# digit_mini.net
KiCad netlist of a schematic drawn in EAGLE
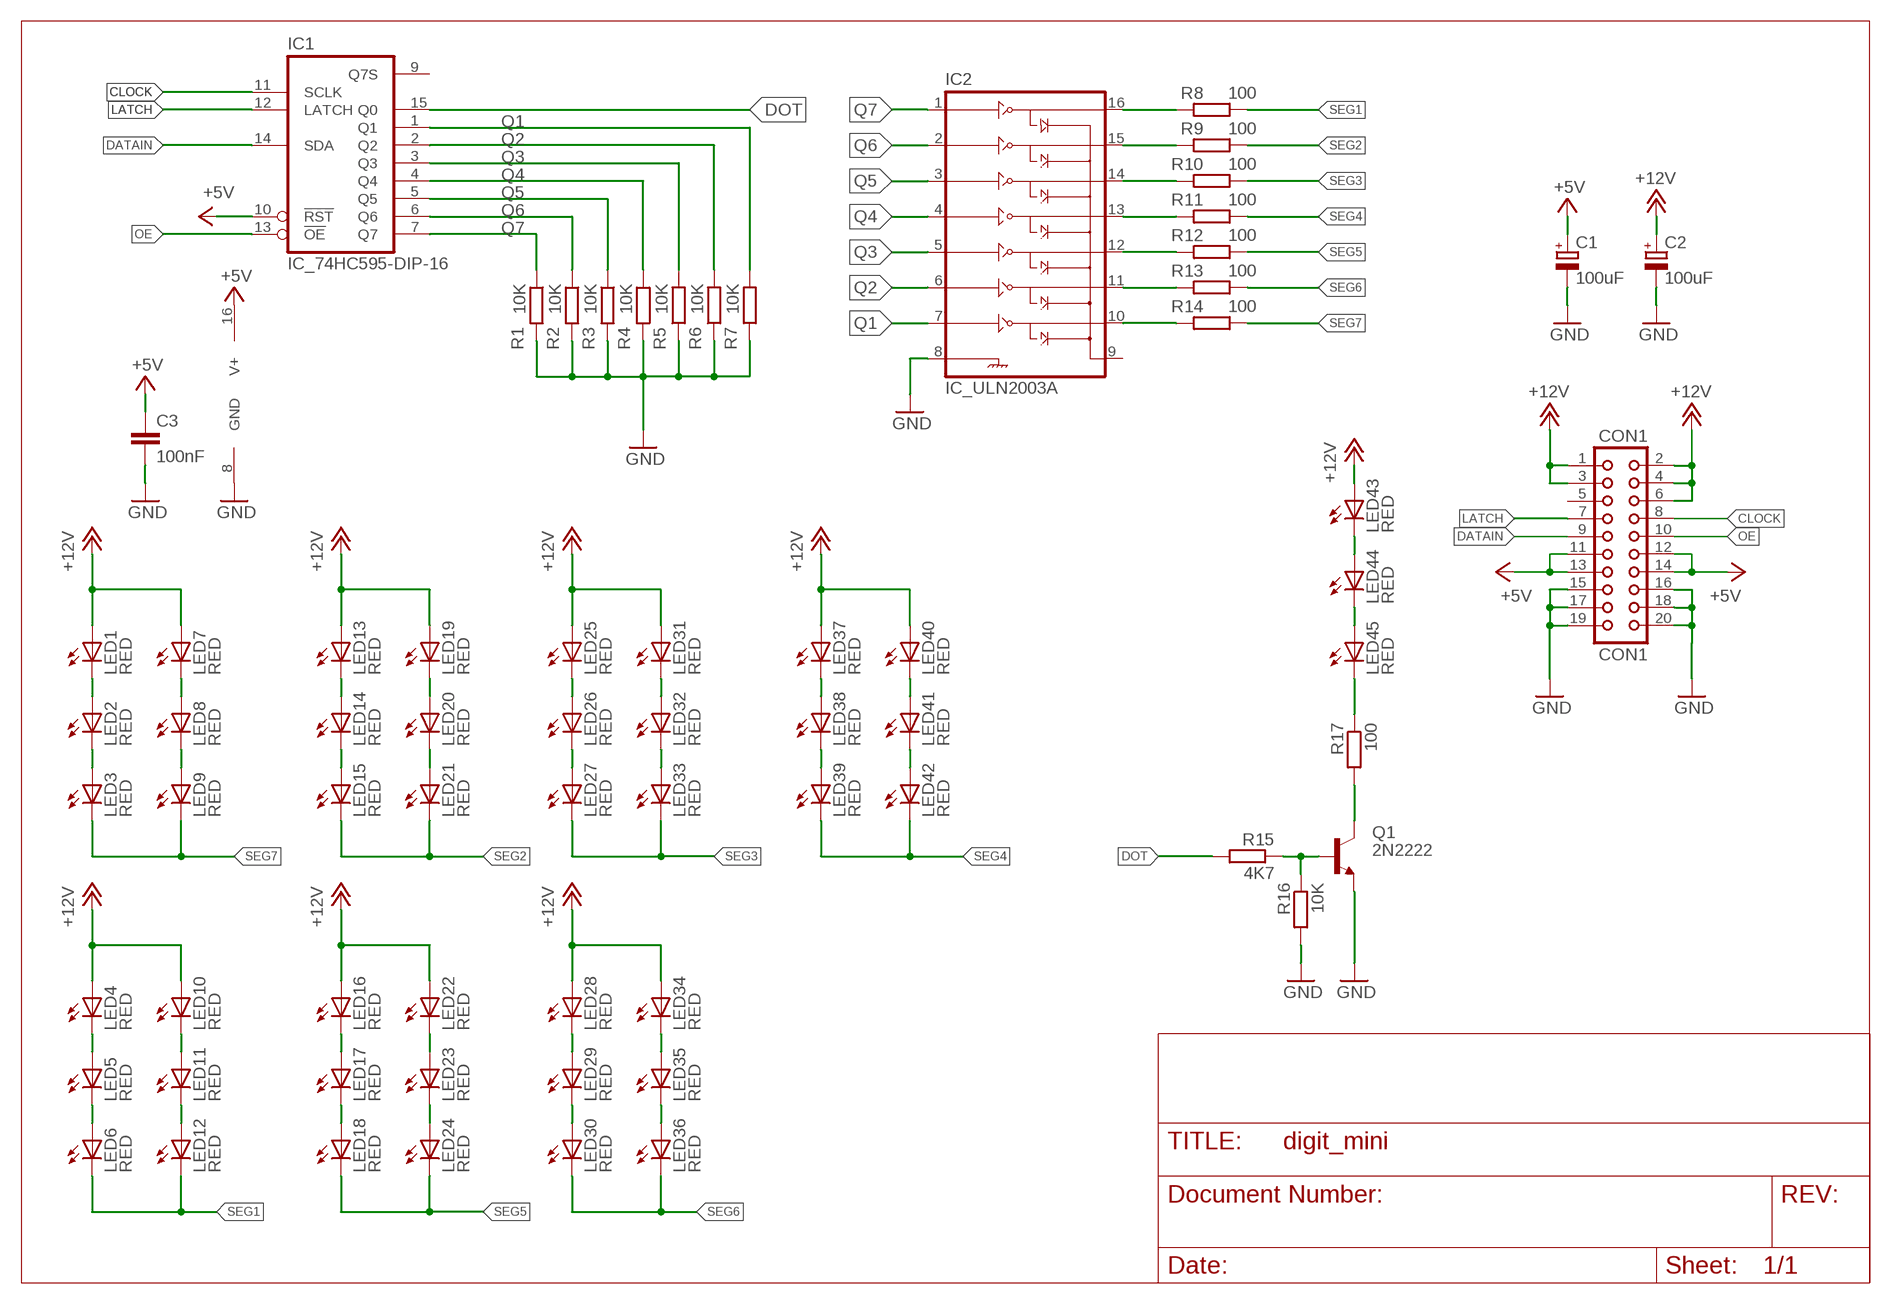
[diagram p0: schematic, sheet 1]

(export (version "E")
  (design (tool "Eeschema 10.0.6"))
  (components
    (comp (ref "C1")
      (value "100uF")
      (footprint "eagle-import:E2,5-7")
      (libsource (lib "eagle-import") (part "CPOL-EUE2.5-7"))
    )
    (comp (ref "C2")
      (value "100uF")
      (footprint "eagle-import:E2,5-7")
      (libsource (lib "eagle-import") (part "CPOL-EUE2.5-7"))
    )
    (comp (ref "C3")
      (value "100nF")
      (footprint "eagle-import:C050-025X075")
      (libsource (lib "eagle-import") (part "C-EU050-025X075"))
    )
    (comp (ref "CON1")
      (value "CON1")
      (footprint "eagle-import:CON20")
      (libsource (lib "eagle-import") (part "CON20"))
    )
    (comp (ref "IC1")
      (value "IC_74HC595-DIP-16")
      (footprint "eagle-import:DIL16")
      (libsource (lib "eagle-import") (part "IC_74HC595-DIP-16"))
    )
    (comp (ref "IC2")
      (value "IC_ULN2003A")
      (footprint "eagle-import:DIL16")
      (libsource (lib "eagle-import") (part "IC_ULN2003A"))
    )
    (comp (ref "LED1")
      (value "RED")
      (footprint "eagle-import:LED5MM")
      (libsource (lib "eagle-import") (part "LED5MM"))
    )
    (comp (ref "LED2")
      (value "RED")
      (footprint "eagle-import:LED5MM")
      (libsource (lib "eagle-import") (part "LED5MM"))
    )
    (comp (ref "LED3")
      (value "RED")
      (footprint "eagle-import:LED5MM")
      (libsource (lib "eagle-import") (part "LED5MM"))
    )
    (comp (ref "LED4")
      (value "RED")
      (footprint "eagle-import:LED5MM")
      (libsource (lib "eagle-import") (part "LED5MM"))
    )
    (comp (ref "LED5")
      (value "RED")
      (footprint "eagle-import:LED5MM")
      (libsource (lib "eagle-import") (part "LED5MM"))
    )
    (comp (ref "LED6")
      (value "RED")
      (footprint "eagle-import:LED5MM")
      (libsource (lib "eagle-import") (part "LED5MM"))
    )
    (comp (ref "LED7")
      (value "RED")
      (footprint "eagle-import:LED5MM")
      (libsource (lib "eagle-import") (part "LED5MM"))
    )
    (comp (ref "LED8")
      (value "RED")
      (footprint "eagle-import:LED5MM")
      (libsource (lib "eagle-import") (part "LED5MM"))
    )
    (comp (ref "LED9")
      (value "RED")
      (footprint "eagle-import:LED5MM")
      (libsource (lib "eagle-import") (part "LED5MM"))
    )
    (comp (ref "LED10")
      (value "RED")
      (footprint "eagle-import:LED5MM")
      (libsource (lib "eagle-import") (part "LED5MM"))
    )
    (comp (ref "LED11")
      (value "RED")
      (footprint "eagle-import:LED5MM")
      (libsource (lib "eagle-import") (part "LED5MM"))
    )
    (comp (ref "LED12")
      (value "RED")
      (footprint "eagle-import:LED5MM")
      (libsource (lib "eagle-import") (part "LED5MM"))
    )
    (comp (ref "LED13")
      (value "RED")
      (footprint "eagle-import:LED5MM")
      (libsource (lib "eagle-import") (part "LED5MM"))
    )
    (comp (ref "LED14")
      (value "RED")
      (footprint "eagle-import:LED5MM")
      (libsource (lib "eagle-import") (part "LED5MM"))
    )
    (comp (ref "LED15")
      (value "RED")
      (footprint "eagle-import:LED5MM")
      (libsource (lib "eagle-import") (part "LED5MM"))
    )
    (comp (ref "LED16")
      (value "RED")
      (footprint "eagle-import:LED5MM")
      (libsource (lib "eagle-import") (part "LED5MM"))
    )
    (comp (ref "LED17")
      (value "RED")
      (footprint "eagle-import:LED5MM")
      (libsource (lib "eagle-import") (part "LED5MM"))
    )
    (comp (ref "LED18")
      (value "RED")
      (footprint "eagle-import:LED5MM")
      (libsource (lib "eagle-import") (part "LED5MM"))
    )
    (comp (ref "LED19")
      (value "RED")
      (footprint "eagle-import:LED5MM")
      (libsource (lib "eagle-import") (part "LED5MM"))
    )
    (comp (ref "LED20")
      (value "RED")
      (footprint "eagle-import:LED5MM")
      (libsource (lib "eagle-import") (part "LED5MM"))
    )
    (comp (ref "LED21")
      (value "RED")
      (footprint "eagle-import:LED5MM")
      (libsource (lib "eagle-import") (part "LED5MM"))
    )
    (comp (ref "LED22")
      (value "RED")
      (footprint "eagle-import:LED5MM")
      (libsource (lib "eagle-import") (part "LED5MM"))
    )
    (comp (ref "LED23")
      (value "RED")
      (footprint "eagle-import:LED5MM")
      (libsource (lib "eagle-import") (part "LED5MM"))
    )
    (comp (ref "LED24")
      (value "RED")
      (footprint "eagle-import:LED5MM")
      (libsource (lib "eagle-import") (part "LED5MM"))
    )
    (comp (ref "LED25")
      (value "RED")
      (footprint "eagle-import:LED5MM")
      (libsource (lib "eagle-import") (part "LED5MM"))
    )
    (comp (ref "LED26")
      (value "RED")
      (footprint "eagle-import:LED5MM")
      (libsource (lib "eagle-import") (part "LED5MM"))
    )
    (comp (ref "LED27")
      (value "RED")
      (footprint "eagle-import:LED5MM")
      (libsource (lib "eagle-import") (part "LED5MM"))
    )
    (comp (ref "LED28")
      (value "RED")
      (footprint "eagle-import:LED5MM")
      (libsource (lib "eagle-import") (part "LED5MM"))
    )
    (comp (ref "LED29")
      (value "RED")
      (footprint "eagle-import:LED5MM")
      (libsource (lib "eagle-import") (part "LED5MM"))
    )
    (comp (ref "LED30")
      (value "RED")
      (footprint "eagle-import:LED5MM")
      (libsource (lib "eagle-import") (part "LED5MM"))
    )
    (comp (ref "LED31")
      (value "RED")
      (footprint "eagle-import:LED5MM")
      (libsource (lib "eagle-import") (part "LED5MM"))
    )
    (comp (ref "LED32")
      (value "RED")
      (footprint "eagle-import:LED5MM")
      (libsource (lib "eagle-import") (part "LED5MM"))
    )
    (comp (ref "LED33")
      (value "RED")
      (footprint "eagle-import:LED5MM")
      (libsource (lib "eagle-import") (part "LED5MM"))
    )
    (comp (ref "LED34")
      (value "RED")
      (footprint "eagle-import:LED5MM")
      (libsource (lib "eagle-import") (part "LED5MM"))
    )
    (comp (ref "LED35")
      (value "RED")
      (footprint "eagle-import:LED5MM")
      (libsource (lib "eagle-import") (part "LED5MM"))
    )
    (comp (ref "LED36")
      (value "RED")
      (footprint "eagle-import:LED5MM")
      (libsource (lib "eagle-import") (part "LED5MM"))
    )
    (comp (ref "LED37")
      (value "RED")
      (footprint "eagle-import:LED5MM")
      (libsource (lib "eagle-import") (part "LED5MM"))
    )
    (comp (ref "LED38")
      (value "RED")
      (footprint "eagle-import:LED5MM")
      (libsource (lib "eagle-import") (part "LED5MM"))
    )
    (comp (ref "LED39")
      (value "RED")
      (footprint "eagle-import:LED5MM")
      (libsource (lib "eagle-import") (part "LED5MM"))
    )
    (comp (ref "LED40")
      (value "RED")
      (footprint "eagle-import:LED5MM")
      (libsource (lib "eagle-import") (part "LED5MM"))
    )
    (comp (ref "LED41")
      (value "RED")
      (footprint "eagle-import:LED5MM")
      (libsource (lib "eagle-import") (part "LED5MM"))
    )
    (comp (ref "LED42")
      (value "RED")
      (footprint "eagle-import:LED5MM")
      (libsource (lib "eagle-import") (part "LED5MM"))
    )
    (comp (ref "LED43")
      (value "RED")
      (footprint "eagle-import:LED5MM")
      (libsource (lib "eagle-import") (part "LED5MM"))
    )
    (comp (ref "LED44")
      (value "RED")
      (footprint "eagle-import:LED5MM")
      (libsource (lib "eagle-import") (part "LED5MM"))
    )
    (comp (ref "LED45")
      (value "RED")
      (footprint "eagle-import:LED5MM")
      (libsource (lib "eagle-import") (part "LED5MM"))
    )
    (comp (ref "Q1")
      (value "2N2222")
      (footprint "eagle-import:TO92-E1")
      (libsource (lib "eagle-import") (part "-NPN-TO92-E1"))
    )
    (comp (ref "R1")
      (value "10K")
      (footprint "eagle-import:0207_12")
      (libsource (lib "eagle-import") (part "R-EU_0207/12"))
    )
    (comp (ref "R2")
      (value "10K")
      (footprint "eagle-import:0207_12")
      (libsource (lib "eagle-import") (part "R-EU_0207/12"))
    )
    (comp (ref "R3")
      (value "10K")
      (footprint "eagle-import:0207_12")
      (libsource (lib "eagle-import") (part "R-EU_0207/12"))
    )
    (comp (ref "R4")
      (value "10K")
      (footprint "eagle-import:0207_12")
      (libsource (lib "eagle-import") (part "R-EU_0207/12"))
    )
    (comp (ref "R5")
      (value "10K")
      (footprint "eagle-import:0207_12")
      (libsource (lib "eagle-import") (part "R-EU_0207/12"))
    )
    (comp (ref "R6")
      (value "10K")
      (footprint "eagle-import:0207_12")
      (libsource (lib "eagle-import") (part "R-EU_0207/12"))
    )
    (comp (ref "R7")
      (value "10K")
      (footprint "eagle-import:0207_12")
      (libsource (lib "eagle-import") (part "R-EU_0207/12"))
    )
    (comp (ref "R8")
      (value "100")
      (footprint "eagle-import:0207_12")
      (libsource (lib "eagle-import") (part "R-EU_0207/12"))
    )
    (comp (ref "R9")
      (value "100")
      (footprint "eagle-import:0207_12")
      (libsource (lib "eagle-import") (part "R-EU_0207/12"))
    )
    (comp (ref "R10")
      (value "100")
      (footprint "eagle-import:0207_12")
      (libsource (lib "eagle-import") (part "R-EU_0207/12"))
    )
    (comp (ref "R11")
      (value "100")
      (footprint "eagle-import:0207_12")
      (libsource (lib "eagle-import") (part "R-EU_0207/12"))
    )
    (comp (ref "R12")
      (value "100")
      (footprint "eagle-import:0207_12")
      (libsource (lib "eagle-import") (part "R-EU_0207/12"))
    )
    (comp (ref "R13")
      (value "100")
      (footprint "eagle-import:0207_12")
      (libsource (lib "eagle-import") (part "R-EU_0207/12"))
    )
    (comp (ref "R14")
      (value "100")
      (footprint "eagle-import:0207_12")
      (libsource (lib "eagle-import") (part "R-EU_0207/12"))
    )
    (comp (ref "R15")
      (value "4K7")
      (footprint "eagle-import:0207_12")
      (libsource (lib "eagle-import") (part "R-EU_0207/12"))
    )
    (comp (ref "R16")
      (value "10K")
      (footprint "eagle-import:0207_12")
      (libsource (lib "eagle-import") (part "R-EU_0207/12"))
    )
    (comp (ref "R17")
      (value "100")
      (footprint "eagle-import:0207_12")
      (libsource (lib "eagle-import") (part "R-EU_0207/12"))
    )
  )
  (nets
    (net (code "1") (name "+5V") (class "Default")
      (node (ref "C1") (pin "+") (pinfunction "+_+") (pintype "passive"))
      (node (ref "C3") (pin "1") (pinfunction "1_1") (pintype "passive"))
      (node (ref "CON1") (pin "11") (pinfunction "11_11") (pintype "passive"))
      (node (ref "CON1") (pin "12") (pinfunction "12_12") (pintype "passive"))
      (node (ref "CON1") (pin "13") (pinfunction "13_13") (pintype "passive"))
      (node (ref "CON1") (pin "14") (pinfunction "14_14") (pintype "passive"))
      (node (ref "IC1") (pin "10") (pinfunction "~{RST}_10") (pintype "input"))
      (node (ref "IC1") (pin "16") (pinfunction "V+_16") (pintype "power_in"))
    )
    (net (code "2") (name "+12V") (class "Default")
      (node (ref "C2") (pin "+") (pinfunction "+_+") (pintype "passive"))
      (node (ref "CON1") (pin "1") (pinfunction "1_1") (pintype "passive"))
      (node (ref "CON1") (pin "2") (pinfunction "2_2") (pintype "passive"))
      (node (ref "CON1") (pin "3") (pinfunction "3_3") (pintype "passive"))
      (node (ref "CON1") (pin "4") (pinfunction "4_4") (pintype "passive"))
      (node (ref "CON1") (pin "6") (pinfunction "6_6") (pintype "passive"))
      (node (ref "LED1") (pin "A") (pinfunction "A_A") (pintype "passive"))
      (node (ref "LED10") (pin "A") (pinfunction "A_A") (pintype "passive"))
      (node (ref "LED13") (pin "A") (pinfunction "A_A") (pintype "passive"))
      (node (ref "LED16") (pin "A") (pinfunction "A_A") (pintype "passive"))
      (node (ref "LED19") (pin "A") (pinfunction "A_A") (pintype "passive"))
      (node (ref "LED22") (pin "A") (pinfunction "A_A") (pintype "passive"))
      (node (ref "LED25") (pin "A") (pinfunction "A_A") (pintype "passive"))
      (node (ref "LED28") (pin "A") (pinfunction "A_A") (pintype "passive"))
      (node (ref "LED31") (pin "A") (pinfunction "A_A") (pintype "passive"))
      (node (ref "LED34") (pin "A") (pinfunction "A_A") (pintype "passive"))
      (node (ref "LED37") (pin "A") (pinfunction "A_A") (pintype "passive"))
      (node (ref "LED4") (pin "A") (pinfunction "A_A") (pintype "passive"))
      (node (ref "LED40") (pin "A") (pinfunction "A_A") (pintype "passive"))
      (node (ref "LED43") (pin "A") (pinfunction "A_A") (pintype "passive"))
      (node (ref "LED7") (pin "A") (pinfunction "A_A") (pintype "passive"))
    )
    (net (code "3") (name "CLOCK") (class "Default")
      (node (ref "CON1") (pin "8") (pinfunction "8_8") (pintype "passive"))
      (node (ref "IC1") (pin "11") (pinfunction "SCLK_11") (pintype "input"))
    )
    (net (code "4") (name "DATAIN") (class "Default")
      (node (ref "CON1") (pin "9") (pinfunction "9_9") (pintype "passive"))
      (node (ref "IC1") (pin "14") (pinfunction "SDA_14") (pintype "input"))
    )
    (net (code "5") (name "DOT") (class "Default")
      (node (ref "IC1") (pin "15") (pinfunction "Q0_15") (pintype "output"))
      (node (ref "R15") (pin "2") (pinfunction "2_2") (pintype "passive"))
    )
    (net (code "6") (name "GND") (class "Default")
      (node (ref "C1") (pin "-") (pinfunction "-_-") (pintype "passive"))
      (node (ref "C2") (pin "-") (pinfunction "-_-") (pintype "passive"))
      (node (ref "C3") (pin "2") (pinfunction "2_2") (pintype "passive"))
      (node (ref "CON1") (pin "15") (pinfunction "15_15") (pintype "passive"))
      (node (ref "CON1") (pin "16") (pinfunction "16_16") (pintype "passive"))
      (node (ref "CON1") (pin "17") (pinfunction "17_17") (pintype "passive"))
      (node (ref "CON1") (pin "18") (pinfunction "18_18") (pintype "passive"))
      (node (ref "CON1") (pin "19") (pinfunction "19_19") (pintype "passive"))
      (node (ref "CON1") (pin "20") (pinfunction "20_20") (pintype "passive"))
      (node (ref "IC1") (pin "8") (pinfunction "GND_8") (pintype "power_in"))
      (node (ref "IC2") (pin "8") (pinfunction "GND_8") (pintype "bidirectional"))
      (node (ref "Q1") (pin "3") (pinfunction "E_3") (pintype "passive"))
      (node (ref "R1") (pin "2") (pinfunction "2_2") (pintype "passive"))
      (node (ref "R16") (pin "2") (pinfunction "2_2") (pintype "passive"))
      (node (ref "R2") (pin "2") (pinfunction "2_2") (pintype "passive"))
      (node (ref "R3") (pin "2") (pinfunction "2_2") (pintype "passive"))
      (node (ref "R4") (pin "1") (pinfunction "1_1") (pintype "passive"))
      (node (ref "R5") (pin "1") (pinfunction "1_1") (pintype "passive"))
      (node (ref "R6") (pin "1") (pinfunction "1_1") (pintype "passive"))
      (node (ref "R7") (pin "1") (pinfunction "1_1") (pintype "passive"))
    )
    (net (code "7") (name "LATCH") (class "Default")
      (node (ref "CON1") (pin "7") (pinfunction "7_7") (pintype "passive"))
      (node (ref "IC1") (pin "12") (pinfunction "LATCH_12") (pintype "input"))
    )
    (net (code "8") (name "Net-(IC2-1C)") (class "Default")
      (node (ref "IC2") (pin "16") (pinfunction "1C_16") (pintype "bidirectional"))
      (node (ref "R8") (pin "2") (pinfunction "2_2") (pintype "passive"))
    )
    (net (code "9") (name "Net-(IC2-2C)") (class "Default")
      (node (ref "IC2") (pin "15") (pinfunction "2C_15") (pintype "bidirectional"))
      (node (ref "R9") (pin "2") (pinfunction "2_2") (pintype "passive"))
    )
    (net (code "10") (name "Net-(IC2-3C)") (class "Default")
      (node (ref "IC2") (pin "14") (pinfunction "3C_14") (pintype "bidirectional"))
      (node (ref "R10") (pin "2") (pinfunction "2_2") (pintype "passive"))
    )
    (net (code "11") (name "Net-(IC2-4C)") (class "Default")
      (node (ref "IC2") (pin "13") (pinfunction "4C_13") (pintype "bidirectional"))
      (node (ref "R11") (pin "2") (pinfunction "2_2") (pintype "passive"))
    )
    (net (code "12") (name "Net-(IC2-5C)") (class "Default")
      (node (ref "IC2") (pin "12") (pinfunction "5C_12") (pintype "bidirectional"))
      (node (ref "R12") (pin "2") (pinfunction "2_2") (pintype "passive"))
    )
    (net (code "13") (name "Net-(IC2-6C)") (class "Default")
      (node (ref "IC2") (pin "11") (pinfunction "6C_11") (pintype "bidirectional"))
      (node (ref "R13") (pin "2") (pinfunction "2_2") (pintype "passive"))
    )
    (net (code "14") (name "Net-(IC2-7C)") (class "Default")
      (node (ref "IC2") (pin "10") (pinfunction "7C_10") (pintype "bidirectional"))
      (node (ref "R14") (pin "2") (pinfunction "2_2") (pintype "passive"))
    )
    (net (code "15") (name "Net-(LED1-C)") (class "Default")
      (node (ref "LED1") (pin "K") (pinfunction "C_K") (pintype "passive"))
      (node (ref "LED2") (pin "A") (pinfunction "A_A") (pintype "passive"))
    )
    (net (code "16") (name "Net-(LED2-C)") (class "Default")
      (node (ref "LED2") (pin "K") (pinfunction "C_K") (pintype "passive"))
      (node (ref "LED3") (pin "A") (pinfunction "A_A") (pintype "passive"))
    )
    (net (code "17") (name "Net-(LED4-C)") (class "Default")
      (node (ref "LED4") (pin "K") (pinfunction "C_K") (pintype "passive"))
      (node (ref "LED5") (pin "A") (pinfunction "A_A") (pintype "passive"))
    )
    (net (code "18") (name "Net-(LED5-C)") (class "Default")
      (node (ref "LED5") (pin "K") (pinfunction "C_K") (pintype "passive"))
      (node (ref "LED6") (pin "A") (pinfunction "A_A") (pintype "passive"))
    )
    (net (code "19") (name "Net-(LED7-C)") (class "Default")
      (node (ref "LED7") (pin "K") (pinfunction "C_K") (pintype "passive"))
      (node (ref "LED8") (pin "A") (pinfunction "A_A") (pintype "passive"))
    )
    (net (code "20") (name "Net-(LED8-C)") (class "Default")
      (node (ref "LED8") (pin "K") (pinfunction "C_K") (pintype "passive"))
      (node (ref "LED9") (pin "A") (pinfunction "A_A") (pintype "passive"))
    )
    (net (code "21") (name "Net-(LED10-C)") (class "Default")
      (node (ref "LED10") (pin "K") (pinfunction "C_K") (pintype "passive"))
      (node (ref "LED11") (pin "A") (pinfunction "A_A") (pintype "passive"))
    )
    (net (code "22") (name "Net-(LED11-C)") (class "Default")
      (node (ref "LED11") (pin "K") (pinfunction "C_K") (pintype "passive"))
      (node (ref "LED12") (pin "A") (pinfunction "A_A") (pintype "passive"))
    )
    (net (code "23") (name "Net-(LED13-C)") (class "Default")
      (node (ref "LED13") (pin "K") (pinfunction "C_K") (pintype "passive"))
      (node (ref "LED14") (pin "A") (pinfunction "A_A") (pintype "passive"))
    )
    (net (code "24") (name "Net-(LED14-C)") (class "Default")
      (node (ref "LED14") (pin "K") (pinfunction "C_K") (pintype "passive"))
      (node (ref "LED15") (pin "A") (pinfunction "A_A") (pintype "passive"))
    )
    (net (code "25") (name "Net-(LED16-C)") (class "Default")
      (node (ref "LED16") (pin "K") (pinfunction "C_K") (pintype "passive"))
      (node (ref "LED17") (pin "A") (pinfunction "A_A") (pintype "passive"))
    )
    (net (code "26") (name "Net-(LED17-C)") (class "Default")
      (node (ref "LED17") (pin "K") (pinfunction "C_K") (pintype "passive"))
      (node (ref "LED18") (pin "A") (pinfunction "A_A") (pintype "passive"))
    )
    (net (code "27") (name "Net-(LED19-C)") (class "Default")
      (node (ref "LED19") (pin "K") (pinfunction "C_K") (pintype "passive"))
      (node (ref "LED20") (pin "A") (pinfunction "A_A") (pintype "passive"))
    )
    (net (code "28") (name "Net-(LED20-C)") (class "Default")
      (node (ref "LED20") (pin "K") (pinfunction "C_K") (pintype "passive"))
      (node (ref "LED21") (pin "A") (pinfunction "A_A") (pintype "passive"))
    )
    (net (code "29") (name "Net-(LED22-C)") (class "Default")
      (node (ref "LED22") (pin "K") (pinfunction "C_K") (pintype "passive"))
      (node (ref "LED23") (pin "A") (pinfunction "A_A") (pintype "passive"))
    )
    (net (code "30") (name "Net-(LED23-C)") (class "Default")
      (node (ref "LED23") (pin "K") (pinfunction "C_K") (pintype "passive"))
      (node (ref "LED24") (pin "A") (pinfunction "A_A") (pintype "passive"))
    )
    (net (code "31") (name "Net-(LED25-C)") (class "Default")
      (node (ref "LED25") (pin "K") (pinfunction "C_K") (pintype "passive"))
      (node (ref "LED26") (pin "A") (pinfunction "A_A") (pintype "passive"))
    )
    (net (code "32") (name "Net-(LED26-C)") (class "Default")
      (node (ref "LED26") (pin "K") (pinfunction "C_K") (pintype "passive"))
      (node (ref "LED27") (pin "A") (pinfunction "A_A") (pintype "passive"))
    )
    (net (code "33") (name "Net-(LED28-C)") (class "Default")
      (node (ref "LED28") (pin "K") (pinfunction "C_K") (pintype "passive"))
      (node (ref "LED29") (pin "A") (pinfunction "A_A") (pintype "passive"))
    )
    (net (code "34") (name "Net-(LED29-C)") (class "Default")
      (node (ref "LED29") (pin "K") (pinfunction "C_K") (pintype "passive"))
      (node (ref "LED30") (pin "A") (pinfunction "A_A") (pintype "passive"))
    )
    (net (code "35") (name "Net-(LED31-C)") (class "Default")
      (node (ref "LED31") (pin "K") (pinfunction "C_K") (pintype "passive"))
      (node (ref "LED32") (pin "A") (pinfunction "A_A") (pintype "passive"))
    )
    (net (code "36") (name "Net-(LED32-C)") (class "Default")
      (node (ref "LED32") (pin "K") (pinfunction "C_K") (pintype "passive"))
      (node (ref "LED33") (pin "A") (pinfunction "A_A") (pintype "passive"))
    )
    (net (code "37") (name "Net-(LED34-C)") (class "Default")
      (node (ref "LED34") (pin "K") (pinfunction "C_K") (pintype "passive"))
      (node (ref "LED35") (pin "A") (pinfunction "A_A") (pintype "passive"))
    )
    (net (code "38") (name "Net-(LED35-C)") (class "Default")
      (node (ref "LED35") (pin "K") (pinfunction "C_K") (pintype "passive"))
      (node (ref "LED36") (pin "A") (pinfunction "A_A") (pintype "passive"))
    )
    (net (code "39") (name "Net-(LED37-C)") (class "Default")
      (node (ref "LED37") (pin "K") (pinfunction "C_K") (pintype "passive"))
      (node (ref "LED38") (pin "A") (pinfunction "A_A") (pintype "passive"))
    )
    (net (code "40") (name "Net-(LED38-C)") (class "Default")
      (node (ref "LED38") (pin "K") (pinfunction "C_K") (pintype "passive"))
      (node (ref "LED39") (pin "A") (pinfunction "A_A") (pintype "passive"))
    )
    (net (code "41") (name "Net-(LED40-C)") (class "Default")
      (node (ref "LED40") (pin "K") (pinfunction "C_K") (pintype "passive"))
      (node (ref "LED41") (pin "A") (pinfunction "A_A") (pintype "passive"))
    )
    (net (code "42") (name "Net-(LED41-C)") (class "Default")
      (node (ref "LED41") (pin "K") (pinfunction "C_K") (pintype "passive"))
      (node (ref "LED42") (pin "A") (pinfunction "A_A") (pintype "passive"))
    )
    (net (code "43") (name "Net-(LED43-C)") (class "Default")
      (node (ref "LED43") (pin "K") (pinfunction "C_K") (pintype "passive"))
      (node (ref "LED44") (pin "A") (pinfunction "A_A") (pintype "passive"))
    )
    (net (code "44") (name "Net-(LED44-C)") (class "Default")
      (node (ref "LED44") (pin "K") (pinfunction "C_K") (pintype "passive"))
      (node (ref "LED45") (pin "A") (pinfunction "A_A") (pintype "passive"))
    )
    (net (code "45") (name "Net-(LED45-C)") (class "Default")
      (node (ref "LED45") (pin "K") (pinfunction "C_K") (pintype "passive"))
      (node (ref "R17") (pin "1") (pinfunction "1_1") (pintype "passive"))
    )
    (net (code "46") (name "Net-(Q1-B)") (class "Default")
      (node (ref "Q1") (pin "2") (pinfunction "B_2") (pintype "passive"))
      (node (ref "R15") (pin "1") (pinfunction "1_1") (pintype "passive"))
      (node (ref "R16") (pin "1") (pinfunction "1_1") (pintype "passive"))
    )
    (net (code "47") (name "Net-(Q1-C)") (class "Default")
      (node (ref "Q1") (pin "1") (pinfunction "C_1") (pintype "passive"))
      (node (ref "R17") (pin "2") (pinfunction "2_2") (pintype "passive"))
    )
    (net (code "48") (name "OE") (class "Default")
      (node (ref "CON1") (pin "10") (pinfunction "10_10") (pintype "passive"))
      (node (ref "IC1") (pin "13") (pinfunction "~{OE}_13") (pintype "input"))
    )
    (net (code "49") (name "Q1") (class "Default")
      (node (ref "IC1") (pin "1") (pinfunction "Q1_1") (pintype "output"))
      (node (ref "IC2") (pin "7") (pinfunction "7B_7") (pintype "bidirectional"))
      (node (ref "R7") (pin "2") (pinfunction "2_2") (pintype "passive"))
    )
    (net (code "50") (name "Q2") (class "Default")
      (node (ref "IC1") (pin "2") (pinfunction "Q2_2") (pintype "output"))
      (node (ref "IC2") (pin "6") (pinfunction "6B_6") (pintype "bidirectional"))
      (node (ref "R6") (pin "2") (pinfunction "2_2") (pintype "passive"))
    )
    (net (code "51") (name "Q3") (class "Default")
      (node (ref "IC1") (pin "3") (pinfunction "Q3_3") (pintype "output"))
      (node (ref "IC2") (pin "5") (pinfunction "5B_5") (pintype "bidirectional"))
      (node (ref "R5") (pin "2") (pinfunction "2_2") (pintype "passive"))
    )
    (net (code "52") (name "Q4") (class "Default")
      (node (ref "IC1") (pin "4") (pinfunction "Q4_4") (pintype "output"))
      (node (ref "IC2") (pin "4") (pinfunction "4B_4") (pintype "bidirectional"))
      (node (ref "R4") (pin "2") (pinfunction "2_2") (pintype "passive"))
    )
    (net (code "53") (name "Q5") (class "Default")
      (node (ref "IC1") (pin "5") (pinfunction "Q5_5") (pintype "output"))
      (node (ref "IC2") (pin "3") (pinfunction "3B_3") (pintype "bidirectional"))
      (node (ref "R3") (pin "1") (pinfunction "1_1") (pintype "passive"))
    )
    (net (code "54") (name "Q6") (class "Default")
      (node (ref "IC1") (pin "6") (pinfunction "Q6_6") (pintype "output"))
      (node (ref "IC2") (pin "2") (pinfunction "2B_2") (pintype "bidirectional"))
      (node (ref "R2") (pin "1") (pinfunction "1_1") (pintype "passive"))
    )
    (net (code "55") (name "Q7") (class "Default")
      (node (ref "IC1") (pin "7") (pinfunction "Q7_7") (pintype "output"))
      (node (ref "IC2") (pin "1") (pinfunction "1B_1") (pintype "bidirectional"))
      (node (ref "R1") (pin "1") (pinfunction "1_1") (pintype "passive"))
    )
    (net (code "56") (name "SEG1") (class "Default")
      (node (ref "LED12") (pin "K") (pinfunction "C_K") (pintype "passive"))
      (node (ref "LED6") (pin "K") (pinfunction "C_K") (pintype "passive"))
      (node (ref "R8") (pin "1") (pinfunction "1_1") (pintype "passive"))
    )
    (net (code "57") (name "SEG2") (class "Default")
      (node (ref "LED15") (pin "K") (pinfunction "C_K") (pintype "passive"))
      (node (ref "LED21") (pin "K") (pinfunction "C_K") (pintype "passive"))
      (node (ref "R9") (pin "1") (pinfunction "1_1") (pintype "passive"))
    )
    (net (code "58") (name "SEG3") (class "Default")
      (node (ref "LED27") (pin "K") (pinfunction "C_K") (pintype "passive"))
      (node (ref "LED33") (pin "K") (pinfunction "C_K") (pintype "passive"))
      (node (ref "R10") (pin "1") (pinfunction "1_1") (pintype "passive"))
    )
    (net (code "59") (name "SEG4") (class "Default")
      (node (ref "LED39") (pin "K") (pinfunction "C_K") (pintype "passive"))
      (node (ref "LED42") (pin "K") (pinfunction "C_K") (pintype "passive"))
      (node (ref "R11") (pin "1") (pinfunction "1_1") (pintype "passive"))
    )
    (net (code "60") (name "SEG5") (class "Default")
      (node (ref "LED18") (pin "K") (pinfunction "C_K") (pintype "passive"))
      (node (ref "LED24") (pin "K") (pinfunction "C_K") (pintype "passive"))
      (node (ref "R12") (pin "1") (pinfunction "1_1") (pintype "passive"))
    )
    (net (code "61") (name "SEG6") (class "Default")
      (node (ref "LED30") (pin "K") (pinfunction "C_K") (pintype "passive"))
      (node (ref "LED36") (pin "K") (pinfunction "C_K") (pintype "passive"))
      (node (ref "R13") (pin "1") (pinfunction "1_1") (pintype "passive"))
    )
    (net (code "62") (name "SEG7") (class "Default")
      (node (ref "LED3") (pin "K") (pinfunction "C_K") (pintype "passive"))
      (node (ref "LED9") (pin "K") (pinfunction "C_K") (pintype "passive"))
      (node (ref "R14") (pin "1") (pinfunction "1_1") (pintype "passive"))
    )
    (net (code "63") (name "unconnected-(CON1-Pad5)") (class "Default")
      (node (ref "CON1") (pin "5") (pinfunction "5_5") (pintype "passive"))
    )
    (net (code "64") (name "unconnected-(IC1A-Q7S-Pad9)") (class "Default")
      (node (ref "IC1") (pin "9") (pinfunction "Q7S_9") (pintype "output"))
    )
    (net (code "65") (name "unconnected-(IC2-COM-Pad9)") (class "Default")
      (node (ref "IC2") (pin "9") (pinfunction "COM_9") (pintype "bidirectional"))
    )
  )
)
